# Titanium_v0_1.net
KiCad netlist of a schematic drawn in Altium Designer
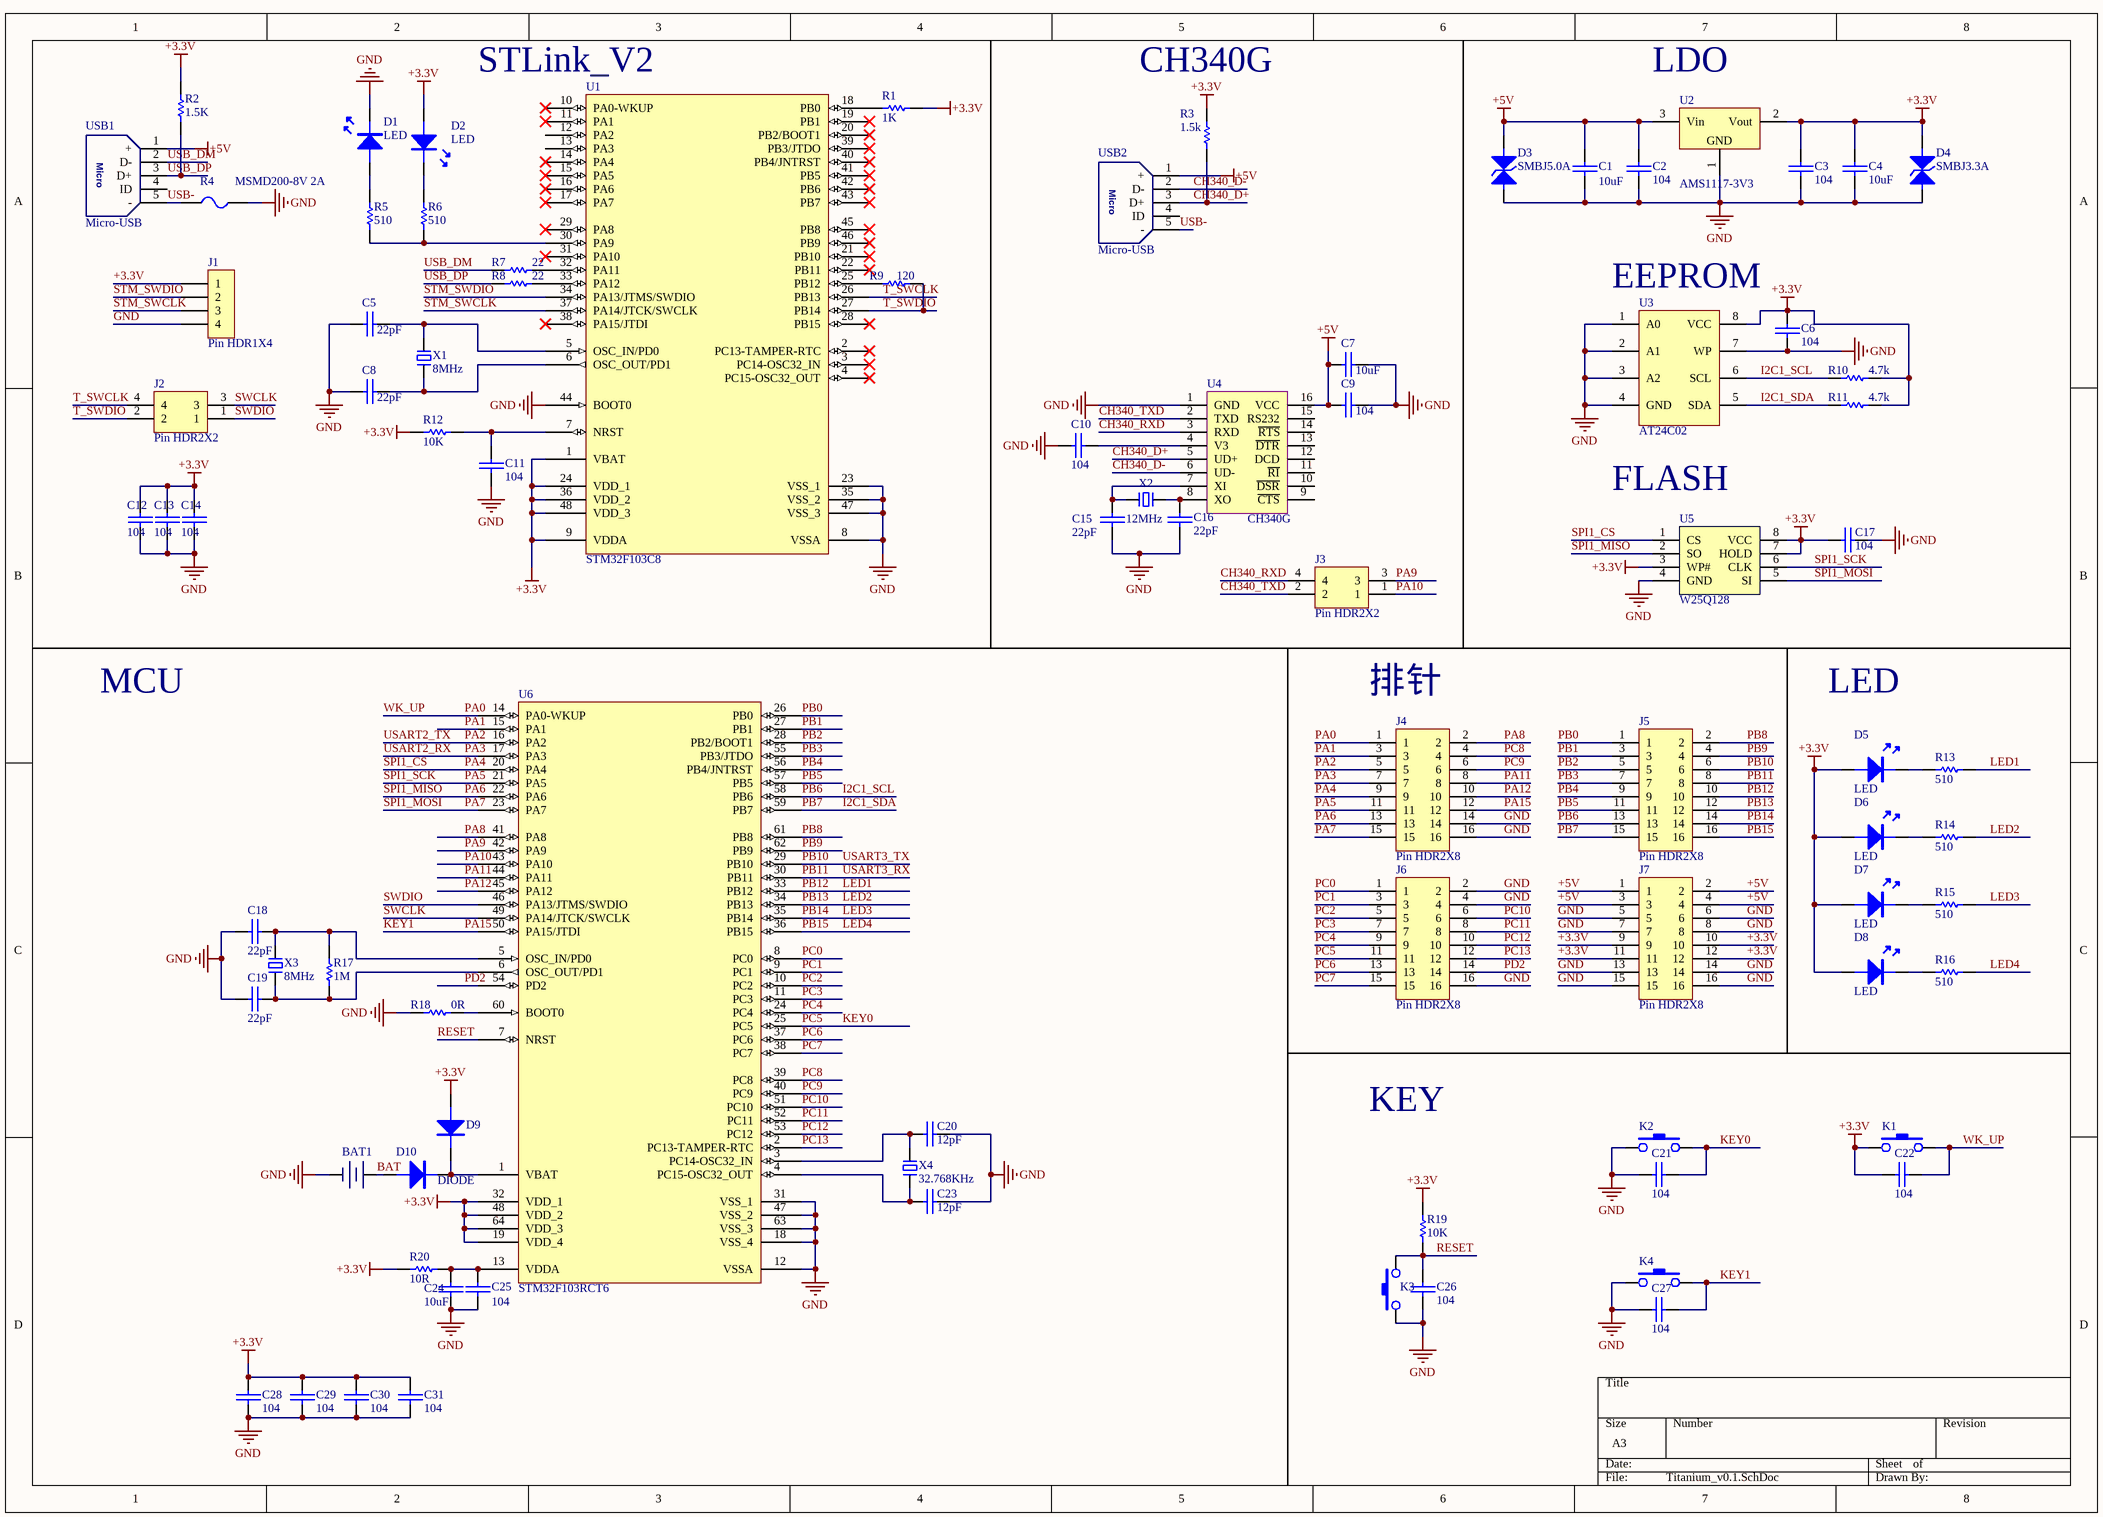
[diagram p0: Titanium_v0.1.SchDoc]

(export (version "E")
  (design (tool "Eeschema 10.0.6"))
  (components
    (comp (ref "BAT1") (value "CR1220") (footprint "CR1220-A") (libsource (lib "纽扣电池座") (part "CR1220")))
    (comp (ref "C1")
      (value "10uF")
      (footprint "1210C")
      (description "无极性电容")
      (libsource (lib "电容") (part "CAP"))
    )
    (comp (ref "C2")
      (value "104")
      (footprint "0603C")
      (description "无极性电容")
      (libsource (lib "电容") (part "CAP"))
    )
    (comp (ref "C3")
      (value "104")
      (footprint "0603C")
      (description "无极性电容")
      (libsource (lib "电容") (part "CAP"))
    )
    (comp (ref "C4")
      (value "10uF")
      (footprint "1210C")
      (description "无极性电容")
      (libsource (lib "电容") (part "CAP"))
    )
    (comp (ref "C5")
      (value "22pF")
      (footprint "0603C")
      (description "无极性电容")
      (libsource (lib "电容") (part "CAP"))
    )
    (comp (ref "C6")
      (value "104")
      (footprint "0603C")
      (description "无极性电容")
      (libsource (lib "电容") (part "CAP"))
    )
    (comp (ref "C7")
      (value "10uF")
      (footprint "0603C")
      (description "无极性电容")
      (libsource (lib "电容") (part "CAP"))
    )
    (comp (ref "C8")
      (value "22pF")
      (footprint "0603C")
      (description "无极性电容")
      (libsource (lib "电容") (part "CAP"))
    )
    (comp (ref "C9")
      (value "104")
      (footprint "0603C")
      (description "无极性电容")
      (libsource (lib "电容") (part "CAP"))
    )
    (comp (ref "C10")
      (value "104")
      (footprint "0603C")
      (description "无极性电容")
      (libsource (lib "电容") (part "CAP"))
    )
    (comp (ref "C11")
      (value "104")
      (footprint "0603C")
      (description "无极性电容")
      (libsource (lib "电容") (part "CAP"))
    )
    (comp (ref "C12")
      (value "104")
      (footprint "0603C")
      (description "无极性电容")
      (libsource (lib "电容") (part "CAP"))
    )
    (comp (ref "C13")
      (value "104")
      (footprint "0603C")
      (description "无极性电容")
      (libsource (lib "电容") (part "CAP"))
    )
    (comp (ref "C14")
      (value "104")
      (footprint "0603C")
      (description "无极性电容")
      (libsource (lib "电容") (part "CAP"))
    )
    (comp (ref "C15")
      (value "22pF")
      (footprint "0603C")
      (description "无极性电容")
      (libsource (lib "电容") (part "CAP"))
    )
    (comp (ref "C16")
      (value "22pF")
      (footprint "0603C")
      (description "无极性电容")
      (libsource (lib "电容") (part "CAP"))
    )
    (comp (ref "C17")
      (value "104")
      (footprint "0603C")
      (description "无极性电容")
      (libsource (lib "电容") (part "CAP"))
    )
    (comp (ref "C18")
      (value "22pF")
      (footprint "0603C")
      (description "无极性电容")
      (libsource (lib "电容") (part "CAP"))
    )
    (comp (ref "C19")
      (value "22pF")
      (footprint "0603C")
      (description "无极性电容")
      (libsource (lib "电容") (part "CAP"))
    )
    (comp (ref "C20")
      (value "12pF")
      (footprint "0603C")
      (description "无极性电容")
      (libsource (lib "电容") (part "CAP"))
    )
    (comp (ref "C21")
      (value "104")
      (footprint "0603C")
      (description "无极性电容")
      (libsource (lib "电容") (part "CAP"))
    )
    (comp (ref "C22")
      (value "104")
      (footprint "0603C")
      (description "无极性电容")
      (libsource (lib "电容") (part "CAP"))
    )
    (comp (ref "C23")
      (value "12pF")
      (footprint "0603C")
      (description "无极性电容")
      (libsource (lib "电容") (part "CAP"))
    )
    (comp (ref "C24")
      (value "10uF")
      (footprint "0603C")
      (description "无极性电容")
      (libsource (lib "电容") (part "CAP"))
    )
    (comp (ref "C25")
      (value "104")
      (footprint "0603C")
      (description "无极性电容")
      (libsource (lib "电容") (part "CAP"))
    )
    (comp (ref "C26")
      (value "104")
      (footprint "0603C")
      (description "无极性电容")
      (libsource (lib "电容") (part "CAP"))
    )
    (comp (ref "C27")
      (value "104")
      (footprint "0603C")
      (description "无极性电容")
      (libsource (lib "电容") (part "CAP"))
    )
    (comp (ref "C28")
      (value "104")
      (footprint "0603C")
      (description "无极性电容")
      (libsource (lib "电容") (part "CAP"))
    )
    (comp (ref "C29")
      (value "104")
      (footprint "0603C")
      (description "无极性电容")
      (libsource (lib "电容") (part "CAP"))
    )
    (comp (ref "C30")
      (value "104")
      (footprint "0603C")
      (description "无极性电容")
      (libsource (lib "电容") (part "CAP"))
    )
    (comp (ref "C31")
      (value "104")
      (footprint "0603C")
      (description "无极性电容")
      (libsource (lib "电容") (part "CAP"))
    )
    (comp (ref "D1") (value "LED") (footprint "LED-0603B") (libsource (lib "LED") (part "LED")))
    (comp (ref "D2") (value "LED") (footprint "LED-0603B") (libsource (lib "LED") (part "LED")))
    (comp (ref "D3")
      (value "SMBJ5.0A")
      (footprint "SMB/DO-214AA")
      (description "双向瞬态抑制二极管")
      (libsource (lib "二极管") (part "TVS"))
    )
    (comp (ref "D4")
      (value "SMBJ3.3A")
      (footprint "SMB/DO-214AA")
      (description "双向瞬态抑制二极管")
      (libsource (lib "二极管") (part "TVS"))
    )
    (comp (ref "D5") (value "LED") (footprint "LED-0603B") (libsource (lib "LED") (part "LED")))
    (comp (ref "D6") (value "LED") (footprint "LED-0603B") (libsource (lib "LED") (part "LED")))
    (comp (ref "D7") (value "LED") (footprint "LED-0603B") (libsource (lib "LED") (part "LED")))
    (comp (ref "D8") (value "LED") (footprint "LED-0603B") (libsource (lib "LED") (part "LED")))
    (comp (ref "D9")
      (value "DIODE")
      (footprint "LL34")
      (description "普通二极管")
      (libsource (lib "二极管") (part "DIODE"))
    )
    (comp (ref "D10")
      (value "DIODE")
      (footprint "LL34")
      (description "普通二极管")
      (libsource (lib "二极管") (part "DIODE"))
    )
    (comp (ref "J1")
      (value "Pin HDR1X4")
      (footprint "Pin HDR1X4/2.54mm-S")
      (libsource (lib "排针") (part "Pin HDR1X4"))
    )
    (comp (ref "J2")
      (value "Pin HDR2X2")
      (footprint "Pin HDR2X2/2.54mm-S")
      (libsource (lib "排针") (part "Pin HDR2X2"))
    )
    (comp (ref "J3")
      (value "Pin HDR2X2")
      (footprint "Pin HDR2X2/2.54mm-S")
      (libsource (lib "排针") (part "Pin HDR2X2"))
    )
    (comp (ref "J4")
      (value "Pin HDR2X8")
      (footprint "Pin HDR2X8/2.54mm-S")
      (libsource (lib "排针") (part "Pin HDR2X8"))
    )
    (comp (ref "J5")
      (value "Pin HDR2X8")
      (footprint "Pin HDR2X8/2.54mm-S")
      (libsource (lib "排针") (part "Pin HDR2X8"))
    )
    (comp (ref "J6")
      (value "Pin HDR2X8")
      (footprint "Pin HDR2X8/2.54mm-S")
      (libsource (lib "排针") (part "Pin HDR2X8"))
    )
    (comp (ref "J7")
      (value "Pin HDR2X8")
      (footprint "Pin HDR2X8/2.54mm-S")
      (libsource (lib "排针") (part "Pin HDR2X8"))
    )
    (comp (ref "K1") (value "KEY") (footprint "DIP-6X6X5") (libsource (lib "轻触开关") (part "KEY")))
    (comp (ref "K2") (value "KEY") (footprint "DIP-6X6X5") (libsource (lib "轻触开关") (part "KEY")))
    (comp (ref "K3") (value "KEY") (footprint "DIP-6X6X5") (libsource (lib "轻触开关") (part "KEY")))
    (comp (ref "K4") (value "KEY") (footprint "DIP-6X6X5") (libsource (lib "轻触开关") (part "KEY")))
    (comp (ref "R1") (value "1K") (footprint "0603R") (libsource (lib "电阻") (part "RES")))
    (comp (ref "R2") (value "1.5K") (footprint "0603R") (libsource (lib "电阻") (part "RES")))
    (comp (ref "R3") (value "1.5k") (footprint "0603R") (libsource (lib "电阻") (part "RES")))
    (comp (ref "R4")
      (value "MSMD200-8V 2A")
      (footprint "0805R")
      (description "贴片保险丝")
      (fields (field (name "版权归属") "源创客"))
      (libsource (lib "10.1 - 保险丝-晶振") (part "FU"))
    )
    (comp (ref "R5") (value "510") (footprint "0603R") (libsource (lib "电阻") (part "RES")))
    (comp (ref "R6") (value "510") (footprint "0603R") (libsource (lib "电阻") (part "RES")))
    (comp (ref "R7") (value "22") (footprint "0603R") (libsource (lib "电阻") (part "RES")))
    (comp (ref "R8") (value "22") (footprint "0603R") (libsource (lib "电阻") (part "RES")))
    (comp (ref "R9") (value "120") (footprint "0603R") (libsource (lib "电阻") (part "RES")))
    (comp (ref "R10") (value "4.7k") (footprint "0603R") (libsource (lib "电阻") (part "RES")))
    (comp (ref "R11") (value "4.7k") (footprint "0603R") (libsource (lib "电阻") (part "RES")))
    (comp (ref "R12") (value "10K") (footprint "0603R") (libsource (lib "电阻") (part "RES")))
    (comp (ref "R13") (value "510") (footprint "0603R") (libsource (lib "电阻") (part "RES")))
    (comp (ref "R14") (value "510") (footprint "0603R") (libsource (lib "电阻") (part "RES")))
    (comp (ref "R15") (value "510") (footprint "0603R") (libsource (lib "电阻") (part "RES")))
    (comp (ref "R16") (value "510") (footprint "0603R") (libsource (lib "电阻") (part "RES")))
    (comp (ref "R17") (value "1M") (footprint "0603R") (libsource (lib "电阻") (part "RES")))
    (comp (ref "R18") (value "0R") (footprint "0603R") (libsource (lib "电阻") (part "RES")))
    (comp (ref "R19") (value "10K") (footprint "0603R") (libsource (lib "电阻") (part "RES")))
    (comp (ref "R20") (value "10R") (footprint "0603R") (libsource (lib "电阻") (part "RES")))
    (comp (ref "U1")
      (value "STM32F103C8")
      (footprint "LQFP48 7X7")
      (description "Flaah:64/RAM:20/IO:36")
      (fields (field (name "版权归属") "源创客"))
      (libsource (lib "2.1   - STM32系列单片机") (part "STM32F103C8"))
    )
    (comp (ref "U2")
      (value "AMS1117-3V3")
      (footprint "SOT89")
      (description "三端稳压芯片")
      (fields (field (name "版权归属") "源创客"))
      (libsource (lib "1.3   - 电源类芯片") (part "AMS1117"))
    )
    (comp (ref "U3") (value "AT24C02") (footprint "SOP8") (libsource (lib "未分类IC") (part "AT24C02")))
    (comp (ref "U4") (value "CH340G") (footprint "SOP16") (libsource (lib "通讯系列IC") (part "CH340G")))
    (comp (ref "U5") (value "W25Q128") (footprint "SOIC8") (libsource (lib "未分类IC") (part "W25Q128")))
    (comp (ref "U6")
      (value "STM32F103RCT6")
      (footprint "LQFP64 10x10")
      (libsource (lib "STM32系列") (part "STM32F103RCT6"))
    )
    (comp (ref "USB1")
      (value "Micro-USB")
      (footprint "USB-MICRO_A")
      (libsource (lib "USB") (part "Micro-USB"))
    )
    (comp (ref "USB2")
      (value "Micro-USB")
      (footprint "USB-MICRO_A")
      (libsource (lib "USB") (part "Micro-USB"))
    )
    (comp (ref "X1")
      (value "8MHz")
      (footprint "OSC 5032-2P")
      (description "2脚无源脚晶振")
      (fields (field (name "版权归属") "源创客"))
      (libsource (lib "10.1 - 保险丝-晶振") (part "XTAL-2P"))
    )
    (comp (ref "X2")
      (value "12MHz")
      (footprint "OSC HC-49SMD")
      (description "2脚无源脚晶振")
      (fields (field (name "版权归属") "源创客"))
      (libsource (lib "10.1 - 保险丝-晶振") (part "XTAL-2P"))
    )
    (comp (ref "X3")
      (value "8MHz")
      (footprint "OSC 5032-2P")
      (description "2脚无源脚晶振")
      (fields (field (name "版权归属") "源创客"))
      (libsource (lib "10.1 - 保险丝-晶振") (part "XTAL-2P"))
    )
    (comp (ref "X4")
      (value "32.768KHz")
      (footprint "OSC 3215-2P")
      (description "2脚无源脚晶振")
      (fields (field (name "版权归属") "源创客"))
      (libsource (lib "10.1 - 保险丝-晶振") (part "XTAL-2P"))
    )
  )
  (nets
    (net (code "1") (name "+3.3V") (class "Default")
      (node (ref "C12") (pin "1") (pinfunction "1_1") (pintype "passive"))
      (node (ref "C13") (pin "1") (pinfunction "1_1") (pintype "passive"))
      (node (ref "C14") (pin "1") (pinfunction "1_1") (pintype "passive"))
      (node (ref "C17") (pin "2") (pinfunction "2_2") (pintype "passive"))
      (node (ref "C22") (pin "1") (pinfunction "1_1") (pintype "passive"))
      (node (ref "C28") (pin "2") (pinfunction "2_2") (pintype "passive"))
      (node (ref "C29") (pin "2") (pinfunction "2_2") (pintype "passive"))
      (node (ref "C3") (pin "2") (pinfunction "2_2") (pintype "passive"))
      (node (ref "C30") (pin "2") (pinfunction "2_2") (pintype "passive"))
      (node (ref "C31") (pin "2") (pinfunction "2_2") (pintype "passive"))
      (node (ref "C4") (pin "2") (pinfunction "2_2") (pintype "passive"))
      (node (ref "C6") (pin "2") (pinfunction "2_2") (pintype "passive"))
      (node (ref "D2") (pin "A") (pinfunction "A_A") (pintype "passive"))
      (node (ref "D4") (pin "K") (pinfunction "K_K") (pintype "passive"))
      (node (ref "D5") (pin "A") (pinfunction "A_A") (pintype "passive"))
      (node (ref "D6") (pin "A") (pinfunction "A_A") (pintype "passive"))
      (node (ref "D7") (pin "A") (pinfunction "A_A") (pintype "passive"))
      (node (ref "D8") (pin "A") (pinfunction "A_A") (pintype "passive"))
      (node (ref "D9") (pin "A") (pinfunction "A_A") (pintype "passive"))
      (node (ref "J1") (pin "1") (pinfunction "1_1") (pintype "passive"))
      (node (ref "J7") (pin "10") (pinfunction "10_10") (pintype "passive"))
      (node (ref "J7") (pin "11") (pinfunction "11_11") (pintype "passive"))
      (node (ref "J7") (pin "12") (pinfunction "12_12") (pintype "passive"))
      (node (ref "J7") (pin "9") (pinfunction "9_9") (pintype "passive"))
      (node (ref "K1") (pin "1") (pinfunction "1_1") (pintype "passive"))
      (node (ref "R1") (pin "2") (pinfunction "2_2") (pintype "passive"))
      (node (ref "R10") (pin "2") (pinfunction "2_2") (pintype "passive"))
      (node (ref "R11") (pin "2") (pinfunction "2_2") (pintype "passive"))
      (node (ref "R12") (pin "1") (pinfunction "1_1") (pintype "passive"))
      (node (ref "R19") (pin "2") (pinfunction "2_2") (pintype "passive"))
      (node (ref "R2") (pin "2") (pinfunction "2_2") (pintype "passive"))
      (node (ref "R20") (pin "1") (pinfunction "1_1") (pintype "passive"))
      (node (ref "R3") (pin "1") (pinfunction "1_1") (pintype "passive"))
      (node (ref "U1") (pin "1") (pinfunction "VBAT_1") (pintype "power_in"))
      (node (ref "U1") (pin "24") (pinfunction "VDD_1_24") (pintype "power_in"))
      (node (ref "U1") (pin "36") (pinfunction "VDD_2_36") (pintype "power_in"))
      (node (ref "U1") (pin "48") (pinfunction "VDD_3_48") (pintype "power_in"))
      (node (ref "U1") (pin "9") (pinfunction "VDDA_9") (pintype "power_in"))
      (node (ref "U2") (pin "2") (pinfunction "Vout_2") (pintype "passive"))
      (node (ref "U3") (pin "8") (pinfunction "VCC_8") (pintype "passive"))
      (node (ref "U5") (pin "3") (pinfunction "WP#_3") (pintype "passive"))
      (node (ref "U5") (pin "7") (pinfunction "HOLD_7") (pintype "passive"))
      (node (ref "U5") (pin "8") (pinfunction "VCC_8") (pintype "passive"))
      (node (ref "U6") (pin "19") (pinfunction "VDD_4_19") (pintype "power_in"))
      (node (ref "U6") (pin "32") (pinfunction "VDD_1_32") (pintype "power_in"))
      (node (ref "U6") (pin "48") (pinfunction "VDD_2_48") (pintype "power_in"))
      (node (ref "U6") (pin "64") (pinfunction "VDD_3_64") (pintype "power_in"))
    )
    (net (code "2") (name "+5V") (class "Default")
      (node (ref "C1") (pin "2") (pinfunction "2_2") (pintype "passive"))
      (node (ref "C2") (pin "2") (pinfunction "2_2") (pintype "passive"))
      (node (ref "C7") (pin "2") (pinfunction "2_2") (pintype "passive"))
      (node (ref "C9") (pin "2") (pinfunction "2_2") (pintype "passive"))
      (node (ref "D3") (pin "K") (pinfunction "K_K") (pintype "passive"))
      (node (ref "J7") (pin "1") (pinfunction "1_1") (pintype "passive"))
      (node (ref "J7") (pin "2") (pinfunction "2_2") (pintype "passive"))
      (node (ref "J7") (pin "3") (pinfunction "3_3") (pintype "passive"))
      (node (ref "J7") (pin "4") (pinfunction "4_4") (pintype "passive"))
      (node (ref "U2") (pin "3") (pinfunction "Vin_3") (pintype "passive"))
      (node (ref "U4") (pin "16") (pinfunction "VCC_16") (pintype "passive"))
      (node (ref "USB1") (pin "1") (pinfunction "+_1") (pintype "passive"))
      (node (ref "USB2") (pin "1") (pinfunction "+_1") (pintype "passive"))
    )
    (net (code "3") (name "/BAT") (class "Default")
      (node (ref "BAT1") (pin "1") (pinfunction "1_1") (pintype "passive"))
      (node (ref "D10") (pin "A") (pinfunction "A_A") (pintype "passive"))
    )
    (net (code "4") (name "/CH340_D+") (class "Default")
      (node (ref "R3") (pin "2") (pinfunction "2_2") (pintype "passive"))
      (node (ref "U4") (pin "5") (pinfunction "UD+_5") (pintype "passive"))
      (node (ref "USB2") (pin "3") (pinfunction "D+_3") (pintype "passive"))
    )
    (net (code "5") (name "/CH340_D-") (class "Default")
      (node (ref "U4") (pin "6") (pinfunction "UD-_6") (pintype "passive"))
      (node (ref "USB2") (pin "2") (pinfunction "D-_2") (pintype "passive"))
    )
    (net (code "6") (name "/CH340_RXD") (class "Default")
      (node (ref "J3") (pin "4") (pinfunction "4_4") (pintype "passive"))
      (node (ref "U4") (pin "3") (pinfunction "RXD_3") (pintype "passive"))
    )
    (net (code "7") (name "/CH340_TXD") (class "Default")
      (node (ref "J3") (pin "2") (pinfunction "2_2") (pintype "passive"))
      (node (ref "U4") (pin "2") (pinfunction "TXD_2") (pintype "passive"))
    )
    (net (code "8") (name "/I2C1_SCL") (class "Default")
      (node (ref "J5") (pin "13") (pinfunction "13_13") (pintype "passive"))
      (node (ref "R10") (pin "1") (pinfunction "1_1") (pintype "passive"))
      (node (ref "U3") (pin "6") (pinfunction "SCL_6") (pintype "passive"))
      (node (ref "U6") (pin "58") (pinfunction "PB6_58") (pintype "bidirectional"))
    )
    (net (code "9") (name "/I2C1_SDA") (class "Default")
      (node (ref "J5") (pin "15") (pinfunction "15_15") (pintype "passive"))
      (node (ref "R11") (pin "1") (pinfunction "1_1") (pintype "passive"))
      (node (ref "U3") (pin "5") (pinfunction "SDA_5") (pintype "passive"))
      (node (ref "U6") (pin "59") (pinfunction "PB7_59") (pintype "bidirectional"))
    )
    (net (code "10") (name "/KEY0") (class "Default")
      (node (ref "C21") (pin "2") (pinfunction "2_2") (pintype "passive"))
      (node (ref "J6") (pin "11") (pinfunction "11_11") (pintype "passive"))
      (node (ref "K2") (pin "3") (pinfunction "3_3") (pintype "passive"))
      (node (ref "U6") (pin "25") (pinfunction "PC5_25") (pintype "bidirectional"))
    )
    (net (code "11") (name "/KEY1") (class "Default")
      (node (ref "C27") (pin "2") (pinfunction "2_2") (pintype "passive"))
      (node (ref "J4") (pin "12") (pinfunction "12_12") (pintype "passive"))
      (node (ref "K4") (pin "3") (pinfunction "3_3") (pintype "passive"))
      (node (ref "U6") (pin "50") (pinfunction "PA15/JTDI_50") (pintype "bidirectional"))
    )
    (net (code "12") (name "/LED1") (class "Default")
      (node (ref "J5") (pin "10") (pinfunction "10_10") (pintype "passive"))
      (node (ref "R13") (pin "2") (pinfunction "2_2") (pintype "passive"))
      (node (ref "U6") (pin "33") (pinfunction "PB12_33") (pintype "bidirectional"))
    )
    (net (code "13") (name "/LED2") (class "Default")
      (node (ref "J5") (pin "12") (pinfunction "12_12") (pintype "passive"))
      (node (ref "R14") (pin "2") (pinfunction "2_2") (pintype "passive"))
      (node (ref "U6") (pin "34") (pinfunction "PB13_34") (pintype "bidirectional"))
    )
    (net (code "14") (name "/LED3") (class "Default")
      (node (ref "J5") (pin "14") (pinfunction "14_14") (pintype "passive"))
      (node (ref "R15") (pin "2") (pinfunction "2_2") (pintype "passive"))
      (node (ref "U6") (pin "35") (pinfunction "PB14_35") (pintype "bidirectional"))
    )
    (net (code "15") (name "/LED4") (class "Default")
      (node (ref "J5") (pin "16") (pinfunction "16_16") (pintype "passive"))
      (node (ref "R16") (pin "2") (pinfunction "2_2") (pintype "passive"))
      (node (ref "U6") (pin "36") (pinfunction "PB15_36") (pintype "bidirectional"))
    )
    (net (code "16") (name "/PA0") (class "Default")
      (node (ref "C22") (pin "2") (pinfunction "2_2") (pintype "passive"))
      (node (ref "J4") (pin "1") (pinfunction "1_1") (pintype "passive"))
      (node (ref "K1") (pin "3") (pinfunction "3_3") (pintype "passive"))
      (node (ref "U6") (pin "14") (pinfunction "PA0-WKUP_14") (pintype "bidirectional"))
    )
    (net (code "17") (name "/PA1") (class "Default")
      (node (ref "J4") (pin "3") (pinfunction "3_3") (pintype "passive"))
      (node (ref "U6") (pin "15") (pinfunction "PA1_15") (pintype "bidirectional"))
    )
    (net (code "18") (name "/PA2") (class "Default")
      (node (ref "J4") (pin "5") (pinfunction "5_5") (pintype "passive"))
      (node (ref "U6") (pin "16") (pinfunction "PA2_16") (pintype "bidirectional"))
    )
    (net (code "19") (name "/PA3") (class "Default")
      (node (ref "J4") (pin "7") (pinfunction "7_7") (pintype "passive"))
      (node (ref "U6") (pin "17") (pinfunction "PA3_17") (pintype "bidirectional"))
    )
    (net (code "20") (name "/PA4") (class "Default")
      (node (ref "J4") (pin "9") (pinfunction "9_9") (pintype "passive"))
      (node (ref "U5") (pin "1") (pinfunction "CS_1") (pintype "passive"))
      (node (ref "U6") (pin "20") (pinfunction "PA4_20") (pintype "bidirectional"))
    )
    (net (code "21") (name "/PA5") (class "Default")
      (node (ref "J4") (pin "11") (pinfunction "11_11") (pintype "passive"))
      (node (ref "U5") (pin "6") (pinfunction "CLK_6") (pintype "passive"))
      (node (ref "U6") (pin "21") (pinfunction "PA5_21") (pintype "bidirectional"))
    )
    (net (code "22") (name "/PA6") (class "Default")
      (node (ref "J4") (pin "13") (pinfunction "13_13") (pintype "passive"))
      (node (ref "U5") (pin "2") (pinfunction "SO_2") (pintype "passive"))
      (node (ref "U6") (pin "22") (pinfunction "PA6_22") (pintype "bidirectional"))
    )
    (net (code "23") (name "/PA7") (class "Default")
      (node (ref "J4") (pin "15") (pinfunction "15_15") (pintype "passive"))
      (node (ref "U5") (pin "5") (pinfunction "SI_5") (pintype "passive"))
      (node (ref "U6") (pin "23") (pinfunction "PA7_23") (pintype "bidirectional"))
    )
    (net (code "24") (name "/PA8") (class "Default")
      (node (ref "J4") (pin "2") (pinfunction "2_2") (pintype "passive"))
      (node (ref "U6") (pin "41") (pinfunction "PA8_41") (pintype "bidirectional"))
    )
    (net (code "25") (name "/PA9") (class "Default")
      (node (ref "J3") (pin "3") (pinfunction "3_3") (pintype "passive"))
      (node (ref "U6") (pin "42") (pinfunction "PA9_42") (pintype "bidirectional"))
    )
    (net (code "26") (name "/PA10") (class "Default")
      (node (ref "J3") (pin "1") (pinfunction "1_1") (pintype "passive"))
      (node (ref "U6") (pin "43") (pinfunction "PA10_43") (pintype "bidirectional"))
    )
    (net (code "27") (name "/PA11") (class "Default")
      (node (ref "J4") (pin "8") (pinfunction "8_8") (pintype "passive"))
      (node (ref "U6") (pin "44") (pinfunction "PA11_44") (pintype "bidirectional"))
    )
    (net (code "28") (name "/PA12") (class "Default")
      (node (ref "J4") (pin "10") (pinfunction "10_10") (pintype "passive"))
      (node (ref "U6") (pin "45") (pinfunction "PA12_45") (pintype "bidirectional"))
    )
    (net (code "29") (name "/PB0") (class "Default")
      (node (ref "J5") (pin "1") (pinfunction "1_1") (pintype "passive"))
      (node (ref "U6") (pin "26") (pinfunction "PB0_26") (pintype "bidirectional"))
    )
    (net (code "30") (name "/PB1") (class "Default")
      (node (ref "J5") (pin "3") (pinfunction "3_3") (pintype "passive"))
      (node (ref "U6") (pin "27") (pinfunction "PB1_27") (pintype "bidirectional"))
    )
    (net (code "31") (name "/PB2") (class "Default")
      (node (ref "J5") (pin "5") (pinfunction "5_5") (pintype "passive"))
      (node (ref "U6") (pin "28") (pinfunction "PB2/BOOT1_28") (pintype "bidirectional"))
    )
    (net (code "32") (name "/PB3") (class "Default")
      (node (ref "J5") (pin "7") (pinfunction "7_7") (pintype "passive"))
      (node (ref "U6") (pin "55") (pinfunction "PB3/JTDO_55") (pintype "bidirectional"))
    )
    (net (code "33") (name "/PB4") (class "Default")
      (node (ref "J5") (pin "9") (pinfunction "9_9") (pintype "passive"))
      (node (ref "U6") (pin "56") (pinfunction "PB4/JNTRST_56") (pintype "bidirectional"))
    )
    (net (code "34") (name "/PB5") (class "Default")
      (node (ref "J5") (pin "11") (pinfunction "11_11") (pintype "passive"))
      (node (ref "U6") (pin "57") (pinfunction "PB5_57") (pintype "bidirectional"))
    )
    (net (code "35") (name "/PB8") (class "Default")
      (node (ref "J5") (pin "2") (pinfunction "2_2") (pintype "passive"))
      (node (ref "U6") (pin "61") (pinfunction "PB8_61") (pintype "bidirectional"))
    )
    (net (code "36") (name "/PB9") (class "Default")
      (node (ref "J5") (pin "4") (pinfunction "4_4") (pintype "passive"))
      (node (ref "U6") (pin "62") (pinfunction "PB9_62") (pintype "bidirectional"))
    )
    (net (code "37") (name "/PB10") (class "Default")
      (node (ref "J5") (pin "6") (pinfunction "6_6") (pintype "passive"))
      (node (ref "U6") (pin "29") (pinfunction "PB10_29") (pintype "bidirectional"))
    )
    (net (code "38") (name "/PB11") (class "Default")
      (node (ref "J5") (pin "8") (pinfunction "8_8") (pintype "passive"))
      (node (ref "U6") (pin "30") (pinfunction "PB11_30") (pintype "bidirectional"))
    )
    (net (code "39") (name "/PC0") (class "Default")
      (node (ref "J6") (pin "1") (pinfunction "1_1") (pintype "passive"))
      (node (ref "U6") (pin "8") (pinfunction "PC0_8") (pintype "bidirectional"))
    )
    (net (code "40") (name "/PC1") (class "Default")
      (node (ref "J6") (pin "3") (pinfunction "3_3") (pintype "passive"))
      (node (ref "U6") (pin "9") (pinfunction "PC1_9") (pintype "bidirectional"))
    )
    (net (code "41") (name "/PC2") (class "Default")
      (node (ref "J6") (pin "5") (pinfunction "5_5") (pintype "passive"))
      (node (ref "U6") (pin "10") (pinfunction "PC2_10") (pintype "bidirectional"))
    )
    (net (code "42") (name "/PC3") (class "Default")
      (node (ref "J6") (pin "7") (pinfunction "7_7") (pintype "passive"))
      (node (ref "U6") (pin "11") (pinfunction "PC3_11") (pintype "bidirectional"))
    )
    (net (code "43") (name "/PC4") (class "Default")
      (node (ref "J6") (pin "9") (pinfunction "9_9") (pintype "passive"))
      (node (ref "U6") (pin "24") (pinfunction "PC4_24") (pintype "bidirectional"))
    )
    (net (code "44") (name "/PC6") (class "Default")
      (node (ref "J6") (pin "13") (pinfunction "13_13") (pintype "passive"))
      (node (ref "U6") (pin "37") (pinfunction "PC6_37") (pintype "bidirectional"))
    )
    (net (code "45") (name "/PC7") (class "Default")
      (node (ref "J6") (pin "15") (pinfunction "15_15") (pintype "passive"))
      (node (ref "U6") (pin "38") (pinfunction "PC7_38") (pintype "bidirectional"))
    )
    (net (code "46") (name "/PC8") (class "Default")
      (node (ref "J4") (pin "4") (pinfunction "4_4") (pintype "passive"))
      (node (ref "U6") (pin "39") (pinfunction "PC8_39") (pintype "bidirectional"))
    )
    (net (code "47") (name "/PC9") (class "Default")
      (node (ref "J4") (pin "6") (pinfunction "6_6") (pintype "passive"))
      (node (ref "U6") (pin "40") (pinfunction "PC9_40") (pintype "bidirectional"))
    )
    (net (code "48") (name "/PC10") (class "Default")
      (node (ref "J6") (pin "6") (pinfunction "6_6") (pintype "passive"))
      (node (ref "U6") (pin "51") (pinfunction "PC10_51") (pintype "bidirectional"))
    )
    (net (code "49") (name "/PC11") (class "Default")
      (node (ref "J6") (pin "8") (pinfunction "8_8") (pintype "passive"))
      (node (ref "U6") (pin "52") (pinfunction "PC11_52") (pintype "bidirectional"))
    )
    (net (code "50") (name "/PC12") (class "Default")
      (node (ref "J6") (pin "10") (pinfunction "10_10") (pintype "passive"))
      (node (ref "U6") (pin "53") (pinfunction "PC12_53") (pintype "bidirectional"))
    )
    (net (code "51") (name "/PC13") (class "Default")
      (node (ref "J6") (pin "12") (pinfunction "12_12") (pintype "passive"))
      (node (ref "U6") (pin "2") (pinfunction "PC13-TAMPER-RTC_2") (pintype "bidirectional"))
    )
    (net (code "52") (name "/PD2") (class "Default")
      (node (ref "J6") (pin "14") (pinfunction "14_14") (pintype "passive"))
      (node (ref "U6") (pin "54") (pinfunction "PD2_54") (pintype "bidirectional"))
    )
    (net (code "53") (name "/RESET") (class "Default")
      (node (ref "C26") (pin "2") (pinfunction "2_2") (pintype "passive"))
      (node (ref "K3") (pin "3") (pinfunction "3_3") (pintype "passive"))
      (node (ref "R19") (pin "1") (pinfunction "1_1") (pintype "passive"))
      (node (ref "U6") (pin "7") (pinfunction "NRST_7") (pintype "bidirectional"))
    )
    (net (code "54") (name "/STM_SWCLK") (class "Default")
      (node (ref "J1") (pin "3") (pinfunction "3_3") (pintype "passive"))
      (node (ref "U1") (pin "37") (pinfunction "PA14/JTCK/SWCLK_37") (pintype "bidirectional"))
    )
    (net (code "55") (name "/STM_SWDIO") (class "Default")
      (node (ref "J1") (pin "2") (pinfunction "2_2") (pintype "passive"))
      (node (ref "U1") (pin "34") (pinfunction "PA13/JTMS/SWDIO_34") (pintype "bidirectional"))
    )
    (net (code "56") (name "/SWCLK") (class "Default")
      (node (ref "J2") (pin "3") (pinfunction "3_3") (pintype "passive"))
      (node (ref "U6") (pin "49") (pinfunction "PA14/JTCK/SWCLK_49") (pintype "bidirectional"))
    )
    (net (code "57") (name "/SWDIO") (class "Default")
      (node (ref "J2") (pin "1") (pinfunction "1_1") (pintype "passive"))
      (node (ref "U6") (pin "46") (pinfunction "PA13/JTMS/SWDIO_46") (pintype "bidirectional"))
    )
    (net (code "58") (name "/T_SWCLK") (class "Default")
      (node (ref "J2") (pin "4") (pinfunction "4_4") (pintype "passive"))
      (node (ref "U1") (pin "26") (pinfunction "PB13_26") (pintype "bidirectional"))
    )
    (net (code "59") (name "/T_SWDIO") (class "Default")
      (node (ref "J2") (pin "2") (pinfunction "2_2") (pintype "passive"))
      (node (ref "R9") (pin "2") (pinfunction "2_2") (pintype "passive"))
      (node (ref "U1") (pin "27") (pinfunction "PB14_27") (pintype "bidirectional"))
    )
    (net (code "60") (name "/USB-") (class "Default")
      (node (ref "R4") (pin "1") (pinfunction "1_1") (pintype "passive"))
      (node (ref "USB1") (pin "5") (pinfunction "-_5") (pintype "passive"))
      (node (ref "USB2") (pin "5") (pinfunction "-_5") (pintype "passive"))
    )
    (net (code "61") (name "/USB_DM") (class "Default")
      (node (ref "R7") (pin "1") (pinfunction "1_1") (pintype "passive"))
      (node (ref "USB1") (pin "2") (pinfunction "D-_2") (pintype "passive"))
    )
    (net (code "62") (name "/USB_DP") (class "Default")
      (node (ref "R2") (pin "1") (pinfunction "1_1") (pintype "passive"))
      (node (ref "R8") (pin "1") (pinfunction "1_1") (pintype "passive"))
      (node (ref "USB1") (pin "3") (pinfunction "D+_3") (pintype "passive"))
    )
    (net (code "63") (name "GND") (class "Default")
      (node (ref "BAT1") (pin "2") (pinfunction "2_2") (pintype "passive"))
      (node (ref "C1") (pin "1") (pinfunction "1_1") (pintype "passive"))
      (node (ref "C10") (pin "2") (pinfunction "2_2") (pintype "passive"))
      (node (ref "C11") (pin "2") (pinfunction "2_2") (pintype "passive"))
      (node (ref "C12") (pin "2") (pinfunction "2_2") (pintype "passive"))
      (node (ref "C13") (pin "2") (pinfunction "2_2") (pintype "passive"))
      (node (ref "C14") (pin "2") (pinfunction "2_2") (pintype "passive"))
      (node (ref "C15") (pin "1") (pinfunction "1_1") (pintype "passive"))
      (node (ref "C16") (pin "1") (pinfunction "1_1") (pintype "passive"))
      (node (ref "C17") (pin "1") (pinfunction "1_1") (pintype "passive"))
      (node (ref "C18") (pin "1") (pinfunction "1_1") (pintype "passive"))
      (node (ref "C19") (pin "1") (pinfunction "1_1") (pintype "passive"))
      (node (ref "C2") (pin "1") (pinfunction "1_1") (pintype "passive"))
      (node (ref "C20") (pin "1") (pinfunction "1_1") (pintype "passive"))
      (node (ref "C21") (pin "1") (pinfunction "1_1") (pintype "passive"))
      (node (ref "C23") (pin "1") (pinfunction "1_1") (pintype "passive"))
      (node (ref "C24") (pin "1") (pinfunction "1_1") (pintype "passive"))
      (node (ref "C25") (pin "1") (pinfunction "1_1") (pintype "passive"))
      (node (ref "C26") (pin "1") (pinfunction "1_1") (pintype "passive"))
      (node (ref "C27") (pin "1") (pinfunction "1_1") (pintype "passive"))
      (node (ref "C28") (pin "1") (pinfunction "1_1") (pintype "passive"))
      (node (ref "C29") (pin "1") (pinfunction "1_1") (pintype "passive"))
      (node (ref "C3") (pin "1") (pinfunction "1_1") (pintype "passive"))
      (node (ref "C30") (pin "1") (pinfunction "1_1") (pintype "passive"))
      (node (ref "C31") (pin "1") (pinfunction "1_1") (pintype "passive"))
      (node (ref "C4") (pin "1") (pinfunction "1_1") (pintype "passive"))
      (node (ref "C5") (pin "2") (pinfunction "2_2") (pintype "passive"))
      (node (ref "C6") (pin "1") (pinfunction "1_1") (pintype "passive"))
      (node (ref "C7") (pin "1") (pinfunction "1_1") (pintype "passive"))
      (node (ref "C8") (pin "2") (pinfunction "2_2") (pintype "passive"))
      (node (ref "C9") (pin "1") (pinfunction "1_1") (pintype "passive"))
      (node (ref "D1") (pin "K") (pinfunction "K_K") (pintype "passive"))
      (node (ref "D3") (pin "A") (pinfunction "A_A") (pintype "passive"))
      (node (ref "D4") (pin "A") (pinfunction "A_A") (pintype "passive"))
      (node (ref "J1") (pin "4") (pinfunction "4_4") (pintype "passive"))
      (node (ref "J4") (pin "14") (pinfunction "14_14") (pintype "passive"))
      (node (ref "J4") (pin "16") (pinfunction "16_16") (pintype "passive"))
      (node (ref "J6") (pin "16") (pinfunction "16_16") (pintype "passive"))
      (node (ref "J6") (pin "2") (pinfunction "2_2") (pintype "passive"))
      (node (ref "J6") (pin "4") (pinfunction "4_4") (pintype "passive"))
      (node (ref "J7") (pin "13") (pinfunction "13_13") (pintype "passive"))
      (node (ref "J7") (pin "14") (pinfunction "14_14") (pintype "passive"))
      (node (ref "J7") (pin "15") (pinfunction "15_15") (pintype "passive"))
      (node (ref "J7") (pin "16") (pinfunction "16_16") (pintype "passive"))
      (node (ref "J7") (pin "5") (pinfunction "5_5") (pintype "passive"))
      (node (ref "J7") (pin "6") (pinfunction "6_6") (pintype "passive"))
      (node (ref "J7") (pin "7") (pinfunction "7_7") (pintype "passive"))
      (node (ref "J7") (pin "8") (pinfunction "8_8") (pintype "passive"))
      (node (ref "K2") (pin "1") (pinfunction "1_1") (pintype "passive"))
      (node (ref "K3") (pin "1") (pinfunction "1_1") (pintype "passive"))
      (node (ref "K4") (pin "1") (pinfunction "1_1") (pintype "passive"))
      (node (ref "R18") (pin "1") (pinfunction "1_1") (pintype "passive"))
      (node (ref "R4") (pin "2") (pinfunction "2_2") (pintype "passive"))
      (node (ref "U1") (pin "23") (pinfunction "VSS_1_23") (pintype "power_in"))
      (node (ref "U1") (pin "35") (pinfunction "VSS_2_35") (pintype "power_in"))
      (node (ref "U1") (pin "44") (pinfunction "BOOT0_44") (pintype "input"))
      (node (ref "U1") (pin "47") (pinfunction "VSS_3_47") (pintype "power_in"))
      (node (ref "U1") (pin "8") (pinfunction "VSSA_8") (pintype "power_in"))
      (node (ref "U2") (pin "1") (pinfunction "GND_1") (pintype "passive"))
      (node (ref "U3") (pin "1") (pinfunction "A0_1") (pintype "passive"))
      (node (ref "U3") (pin "2") (pinfunction "A1_2") (pintype "passive"))
      (node (ref "U3") (pin "3") (pinfunction "A2_3") (pintype "passive"))
      (node (ref "U3") (pin "4") (pinfunction "GND_4") (pintype "passive"))
      (node (ref "U3") (pin "7") (pinfunction "WP_7") (pintype "passive"))
      (node (ref "U4") (pin "1") (pinfunction "GND_1") (pintype "passive"))
      (node (ref "U5") (pin "4") (pinfunction "GND_4") (pintype "passive"))
      (node (ref "U6") (pin "12") (pinfunction "VSSA_12") (pintype "power_in"))
      (node (ref "U6") (pin "18") (pinfunction "VSS_4_18") (pintype "power_in"))
      (node (ref "U6") (pin "31") (pinfunction "VSS_1_31") (pintype "power_in"))
      (node (ref "U6") (pin "47") (pinfunction "VSS_2_47") (pintype "power_in"))
      (node (ref "U6") (pin "63") (pinfunction "VSS_3_63") (pintype "power_in"))
    )
    (net (code "64") (name "Net-(D1-PadA)") (class "Default")
      (node (ref "D1") (pin "A") (pinfunction "A_A") (pintype "passive"))
      (node (ref "R5") (pin "2") (pinfunction "2_2") (pintype "passive"))
    )
    (net (code "65") (name "Net-(D2-PadK)") (class "Default")
      (node (ref "D2") (pin "K") (pinfunction "K_K") (pintype "passive"))
      (node (ref "R6") (pin "2") (pinfunction "2_2") (pintype "passive"))
    )
    (net (code "66") (name "Net-(D5-PadK)") (class "Default")
      (node (ref "D5") (pin "K") (pinfunction "K_K") (pintype "passive"))
      (node (ref "R13") (pin "1") (pinfunction "1_1") (pintype "passive"))
    )
    (net (code "67") (name "Net-(D6-PadK)") (class "Default")
      (node (ref "D6") (pin "K") (pinfunction "K_K") (pintype "passive"))
      (node (ref "R14") (pin "1") (pinfunction "1_1") (pintype "passive"))
    )
    (net (code "68") (name "Net-(D7-PadK)") (class "Default")
      (node (ref "D7") (pin "K") (pinfunction "K_K") (pintype "passive"))
      (node (ref "R15") (pin "1") (pinfunction "1_1") (pintype "passive"))
    )
    (net (code "69") (name "Net-(D8-PadK)") (class "Default")
      (node (ref "D8") (pin "K") (pinfunction "K_K") (pintype "passive"))
      (node (ref "R16") (pin "1") (pinfunction "1_1") (pintype "passive"))
    )
    (net (code "70") (name "Net-(U1-NRST)") (class "Default")
      (node (ref "C11") (pin "1") (pinfunction "1_1") (pintype "passive"))
      (node (ref "R12") (pin "2") (pinfunction "2_2") (pintype "passive"))
      (node (ref "U1") (pin "7") (pinfunction "NRST_7") (pintype "bidirectional"))
    )
    (net (code "71") (name "Net-(U1-OSC_IN{slash}PD0)") (class "Default")
      (node (ref "C5") (pin "1") (pinfunction "1_1") (pintype "passive"))
      (node (ref "U1") (pin "5") (pinfunction "OSC_IN/PD0_5") (pintype "input"))
      (node (ref "X1") (pin "2") (pinfunction "2_2") (pintype "passive"))
    )
    (net (code "72") (name "Net-(U1-OSC_OUT{slash}PD1)") (class "Default")
      (node (ref "C8") (pin "1") (pinfunction "1_1") (pintype "passive"))
      (node (ref "U1") (pin "6") (pinfunction "OSC_OUT/PD1_6") (pintype "output"))
      (node (ref "X1") (pin "1") (pinfunction "1_1") (pintype "passive"))
    )
    (net (code "73") (name "Net-(U1-PA9)") (class "Default")
      (node (ref "R5") (pin "1") (pinfunction "1_1") (pintype "passive"))
      (node (ref "R6") (pin "1") (pinfunction "1_1") (pintype "passive"))
      (node (ref "U1") (pin "30") (pinfunction "PA9_30") (pintype "bidirectional"))
    )
    (net (code "74") (name "Net-(U1-PA11)") (class "Default")
      (node (ref "R7") (pin "2") (pinfunction "2_2") (pintype "passive"))
      (node (ref "U1") (pin "32") (pinfunction "PA11_32") (pintype "bidirectional"))
    )
    (net (code "75") (name "Net-(U1-PA12)") (class "Default")
      (node (ref "R8") (pin "2") (pinfunction "2_2") (pintype "passive"))
      (node (ref "U1") (pin "33") (pinfunction "PA12_33") (pintype "bidirectional"))
    )
    (net (code "76") (name "Net-(U1-PB0)") (class "Default")
      (node (ref "R1") (pin "1") (pinfunction "1_1") (pintype "passive"))
      (node (ref "U1") (pin "18") (pinfunction "PB0_18") (pintype "bidirectional"))
    )
    (net (code "77") (name "Net-(U1-PB12)") (class "Default")
      (node (ref "R9") (pin "1") (pinfunction "1_1") (pintype "passive"))
      (node (ref "U1") (pin "25") (pinfunction "PB12_25") (pintype "bidirectional"))
    )
    (net (code "78") (name "Net-(U4-V3)") (class "Default")
      (node (ref "C10") (pin "1") (pinfunction "1_1") (pintype "passive"))
      (node (ref "U4") (pin "4") (pinfunction "V3_4") (pintype "passive"))
    )
    (net (code "79") (name "Net-(U4-XI)") (class "Default")
      (node (ref "C15") (pin "2") (pinfunction "2_2") (pintype "passive"))
      (node (ref "U4") (pin "7") (pinfunction "XI_7") (pintype "passive"))
      (node (ref "X2") (pin "2") (pinfunction "2_2") (pintype "passive"))
    )
    (net (code "80") (name "Net-(U4-XO)") (class "Default")
      (node (ref "C16") (pin "2") (pinfunction "2_2") (pintype "passive"))
      (node (ref "U4") (pin "8") (pinfunction "XO_8") (pintype "passive"))
      (node (ref "X2") (pin "1") (pinfunction "1_1") (pintype "passive"))
    )
    (net (code "81") (name "Net-(U6-BOOT0)") (class "Default")
      (node (ref "R18") (pin "2") (pinfunction "2_2") (pintype "passive"))
      (node (ref "U6") (pin "60") (pinfunction "BOOT0_60") (pintype "input"))
    )
    (net (code "82") (name "Net-(U6-OSC_IN{slash}PD0)") (class "Default")
      (node (ref "C18") (pin "2") (pinfunction "2_2") (pintype "passive"))
      (node (ref "R17") (pin "2") (pinfunction "2_2") (pintype "passive"))
      (node (ref "U6") (pin "5") (pinfunction "OSC_IN/PD0_5") (pintype "input"))
      (node (ref "X3") (pin "2") (pinfunction "2_2") (pintype "passive"))
    )
    (net (code "83") (name "Net-(U6-OSC_OUT{slash}PD1)") (class "Default")
      (node (ref "C19") (pin "2") (pinfunction "2_2") (pintype "passive"))
      (node (ref "R17") (pin "1") (pinfunction "1_1") (pintype "passive"))
      (node (ref "U6") (pin "6") (pinfunction "OSC_OUT/PD1_6") (pintype "output"))
      (node (ref "X3") (pin "1") (pinfunction "1_1") (pintype "passive"))
    )
    (net (code "84") (name "Net-(U6-PC14-OSC32_IN)") (class "Default")
      (node (ref "C20") (pin "2") (pinfunction "2_2") (pintype "passive"))
      (node (ref "U6") (pin "3") (pinfunction "PC14-OSC32_IN_3") (pintype "bidirectional"))
      (node (ref "X4") (pin "1") (pinfunction "1_1") (pintype "passive"))
    )
    (net (code "85") (name "Net-(U6-PC15-OSC32_OUT)") (class "Default")
      (node (ref "C23") (pin "2") (pinfunction "2_2") (pintype "passive"))
      (node (ref "U6") (pin "4") (pinfunction "PC15-OSC32_OUT_4") (pintype "bidirectional"))
      (node (ref "X4") (pin "2") (pinfunction "2_2") (pintype "passive"))
    )
    (net (code "86") (name "Net-(U6-VBAT)") (class "Default")
      (node (ref "D10") (pin "K") (pinfunction "K_K") (pintype "passive"))
      (node (ref "D9") (pin "K") (pinfunction "K_K") (pintype "passive"))
      (node (ref "U6") (pin "1") (pinfunction "VBAT_1") (pintype "power_in"))
    )
    (net (code "87") (name "Net-(U6-VDDA)") (class "Default")
      (node (ref "C24") (pin "2") (pinfunction "2_2") (pintype "passive"))
      (node (ref "C25") (pin "2") (pinfunction "2_2") (pintype "passive"))
      (node (ref "R20") (pin "2") (pinfunction "2_2") (pintype "passive"))
      (node (ref "U6") (pin "13") (pinfunction "VDDA_13") (pintype "power_in"))
    )
    (net (code "88") (name "unconnected-(U1-PA0-WKUP-Pad10)") (class "Default")
      (node (ref "U1") (pin "10") (pinfunction "PA0-WKUP_10") (pintype "bidirectional+no_connect"))
    )
    (net (code "89") (name "unconnected-(U1-PA1-Pad11)") (class "Default")
      (node (ref "U1") (pin "11") (pinfunction "PA1_11") (pintype "bidirectional+no_connect"))
    )
    (net (code "90") (name "unconnected-(U1-PA2-Pad12)") (class "Default")
      (node (ref "U1") (pin "12") (pinfunction "PA2_12") (pintype "bidirectional"))
    )
    (net (code "91") (name "unconnected-(U1-PA3-Pad13)") (class "Default")
      (node (ref "U1") (pin "13") (pinfunction "PA3_13") (pintype "bidirectional"))
    )
    (net (code "92") (name "unconnected-(U1-PA4-Pad14)") (class "Default")
      (node (ref "U1") (pin "14") (pinfunction "PA4_14") (pintype "bidirectional+no_connect"))
    )
    (net (code "93") (name "unconnected-(U1-PA5-Pad15)") (class "Default")
      (node (ref "U1") (pin "15") (pinfunction "PA5_15") (pintype "bidirectional+no_connect"))
    )
    (net (code "94") (name "unconnected-(U1-PA6-Pad16)") (class "Default")
      (node (ref "U1") (pin "16") (pinfunction "PA6_16") (pintype "bidirectional+no_connect"))
    )
    (net (code "95") (name "unconnected-(U1-PA7-Pad17)") (class "Default")
      (node (ref "U1") (pin "17") (pinfunction "PA7_17") (pintype "bidirectional+no_connect"))
    )
    (net (code "96") (name "unconnected-(U1-PA8-Pad29)") (class "Default")
      (node (ref "U1") (pin "29") (pinfunction "PA8_29") (pintype "bidirectional+no_connect"))
    )
    (net (code "97") (name "unconnected-(U1-PA10-Pad31)") (class "Default")
      (node (ref "U1") (pin "31") (pinfunction "PA10_31") (pintype "bidirectional+no_connect"))
    )
    (net (code "98") (name "unconnected-(U1-PA15{slash}JTDI-Pad38)") (class "Default")
      (node (ref "U1") (pin "38") (pinfunction "PA15/JTDI_38") (pintype "bidirectional+no_connect"))
    )
    (net (code "99") (name "unconnected-(U1-PB1-Pad19)") (class "Default")
      (node (ref "U1") (pin "19") (pinfunction "PB1_19") (pintype "bidirectional+no_connect"))
    )
    (net (code "100") (name "unconnected-(U1-PB2{slash}BOOT1-Pad20)") (class "Default")
      (node (ref "U1") (pin "20") (pinfunction "PB2/BOOT1_20") (pintype "bidirectional+no_connect"))
    )
    (net (code "101") (name "unconnected-(U1-PB3{slash}JTDO-Pad39)") (class "Default")
      (node (ref "U1") (pin "39") (pinfunction "PB3/JTDO_39") (pintype "bidirectional+no_connect"))
    )
    (net (code "102") (name "unconnected-(U1-PB4{slash}JNTRST-Pad40)") (class "Default")
      (node (ref "U1") (pin "40") (pinfunction "PB4/JNTRST_40") (pintype "bidirectional+no_connect"))
    )
    (net (code "103") (name "unconnected-(U1-PB5-Pad41)") (class "Default")
      (node (ref "U1") (pin "41") (pinfunction "PB5_41") (pintype "bidirectional+no_connect"))
    )
    (net (code "104") (name "unconnected-(U1-PB6-Pad42)") (class "Default")
      (node (ref "U1") (pin "42") (pinfunction "PB6_42") (pintype "bidirectional+no_connect"))
    )
    (net (code "105") (name "unconnected-(U1-PB7-Pad43)") (class "Default")
      (node (ref "U1") (pin "43") (pinfunction "PB7_43") (pintype "bidirectional+no_connect"))
    )
    (net (code "106") (name "unconnected-(U1-PB8-Pad45)") (class "Default")
      (node (ref "U1") (pin "45") (pinfunction "PB8_45") (pintype "bidirectional+no_connect"))
    )
    (net (code "107") (name "unconnected-(U1-PB9-Pad46)") (class "Default")
      (node (ref "U1") (pin "46") (pinfunction "PB9_46") (pintype "bidirectional+no_connect"))
    )
    (net (code "108") (name "unconnected-(U1-PB10-Pad21)") (class "Default")
      (node (ref "U1") (pin "21") (pinfunction "PB10_21") (pintype "bidirectional+no_connect"))
    )
    (net (code "109") (name "unconnected-(U1-PB11-Pad22)") (class "Default")
      (node (ref "U1") (pin "22") (pinfunction "PB11_22") (pintype "bidirectional+no_connect"))
    )
    (net (code "110") (name "unconnected-(U1-PB15-Pad28)") (class "Default")
      (node (ref "U1") (pin "28") (pinfunction "PB15_28") (pintype "bidirectional+no_connect"))
    )
    (net (code "111") (name "unconnected-(U1-PC13-TAMPER-RTC-Pad2)") (class "Default")
      (node (ref "U1") (pin "2") (pinfunction "PC13-TAMPER-RTC_2") (pintype "bidirectional+no_connect"))
    )
    (net (code "112") (name "unconnected-(U1-PC14-OSC32_IN-Pad3)") (class "Default")
      (node (ref "U1") (pin "3") (pinfunction "PC14-OSC32_IN_3") (pintype "bidirectional+no_connect"))
    )
    (net (code "113") (name "unconnected-(U1-PC15-OSC32_OUT-Pad4)") (class "Default")
      (node (ref "U1") (pin "4") (pinfunction "PC15-OSC32_OUT_4") (pintype "bidirectional+no_connect"))
    )
    (net (code "114") (name "unconnected-(U4-DCD-Pad12)") (class "Default")
      (node (ref "U4") (pin "12") (pinfunction "DCD_12") (pintype "passive"))
    )
    (net (code "115") (name "unconnected-(U4-RS232-Pad15)") (class "Default")
      (node (ref "U4") (pin "15") (pinfunction "RS232_15") (pintype "passive"))
    )
    (net (code "116") (name "unconnected-(U4-~{CTS}-Pad9)") (class "Default")
      (node (ref "U4") (pin "9") (pinfunction "~{CTS}_9") (pintype "passive"))
    )
    (net (code "117") (name "unconnected-(U4-~{DSR}-Pad10)") (class "Default")
      (node (ref "U4") (pin "10") (pinfunction "~{DSR}_10") (pintype "passive"))
    )
    (net (code "118") (name "unconnected-(U4-~{DTR}-Pad13)") (class "Default")
      (node (ref "U4") (pin "13") (pinfunction "~{DTR}_13") (pintype "passive"))
    )
    (net (code "119") (name "unconnected-(U4-~{RI}-Pad11)") (class "Default")
      (node (ref "U4") (pin "11") (pinfunction "~{RI}_11") (pintype "passive"))
    )
    (net (code "120") (name "unconnected-(U4-~{RTS}-Pad14)") (class "Default")
      (node (ref "U4") (pin "14") (pinfunction "~{RTS}_14") (pintype "passive"))
    )
    (net (code "121") (name "unconnected-(USB1-ID-Pad4)") (class "Default")
      (node (ref "USB1") (pin "4") (pinfunction "ID_4") (pintype "passive"))
    )
    (net (code "122") (name "unconnected-(USB2-ID-Pad4)") (class "Default")
      (node (ref "USB2") (pin "4") (pinfunction "ID_4") (pintype "passive"))
    )
  )
)
